# 18_ETH.net
KiCad netlist of a schematic drawn in Altium Designer
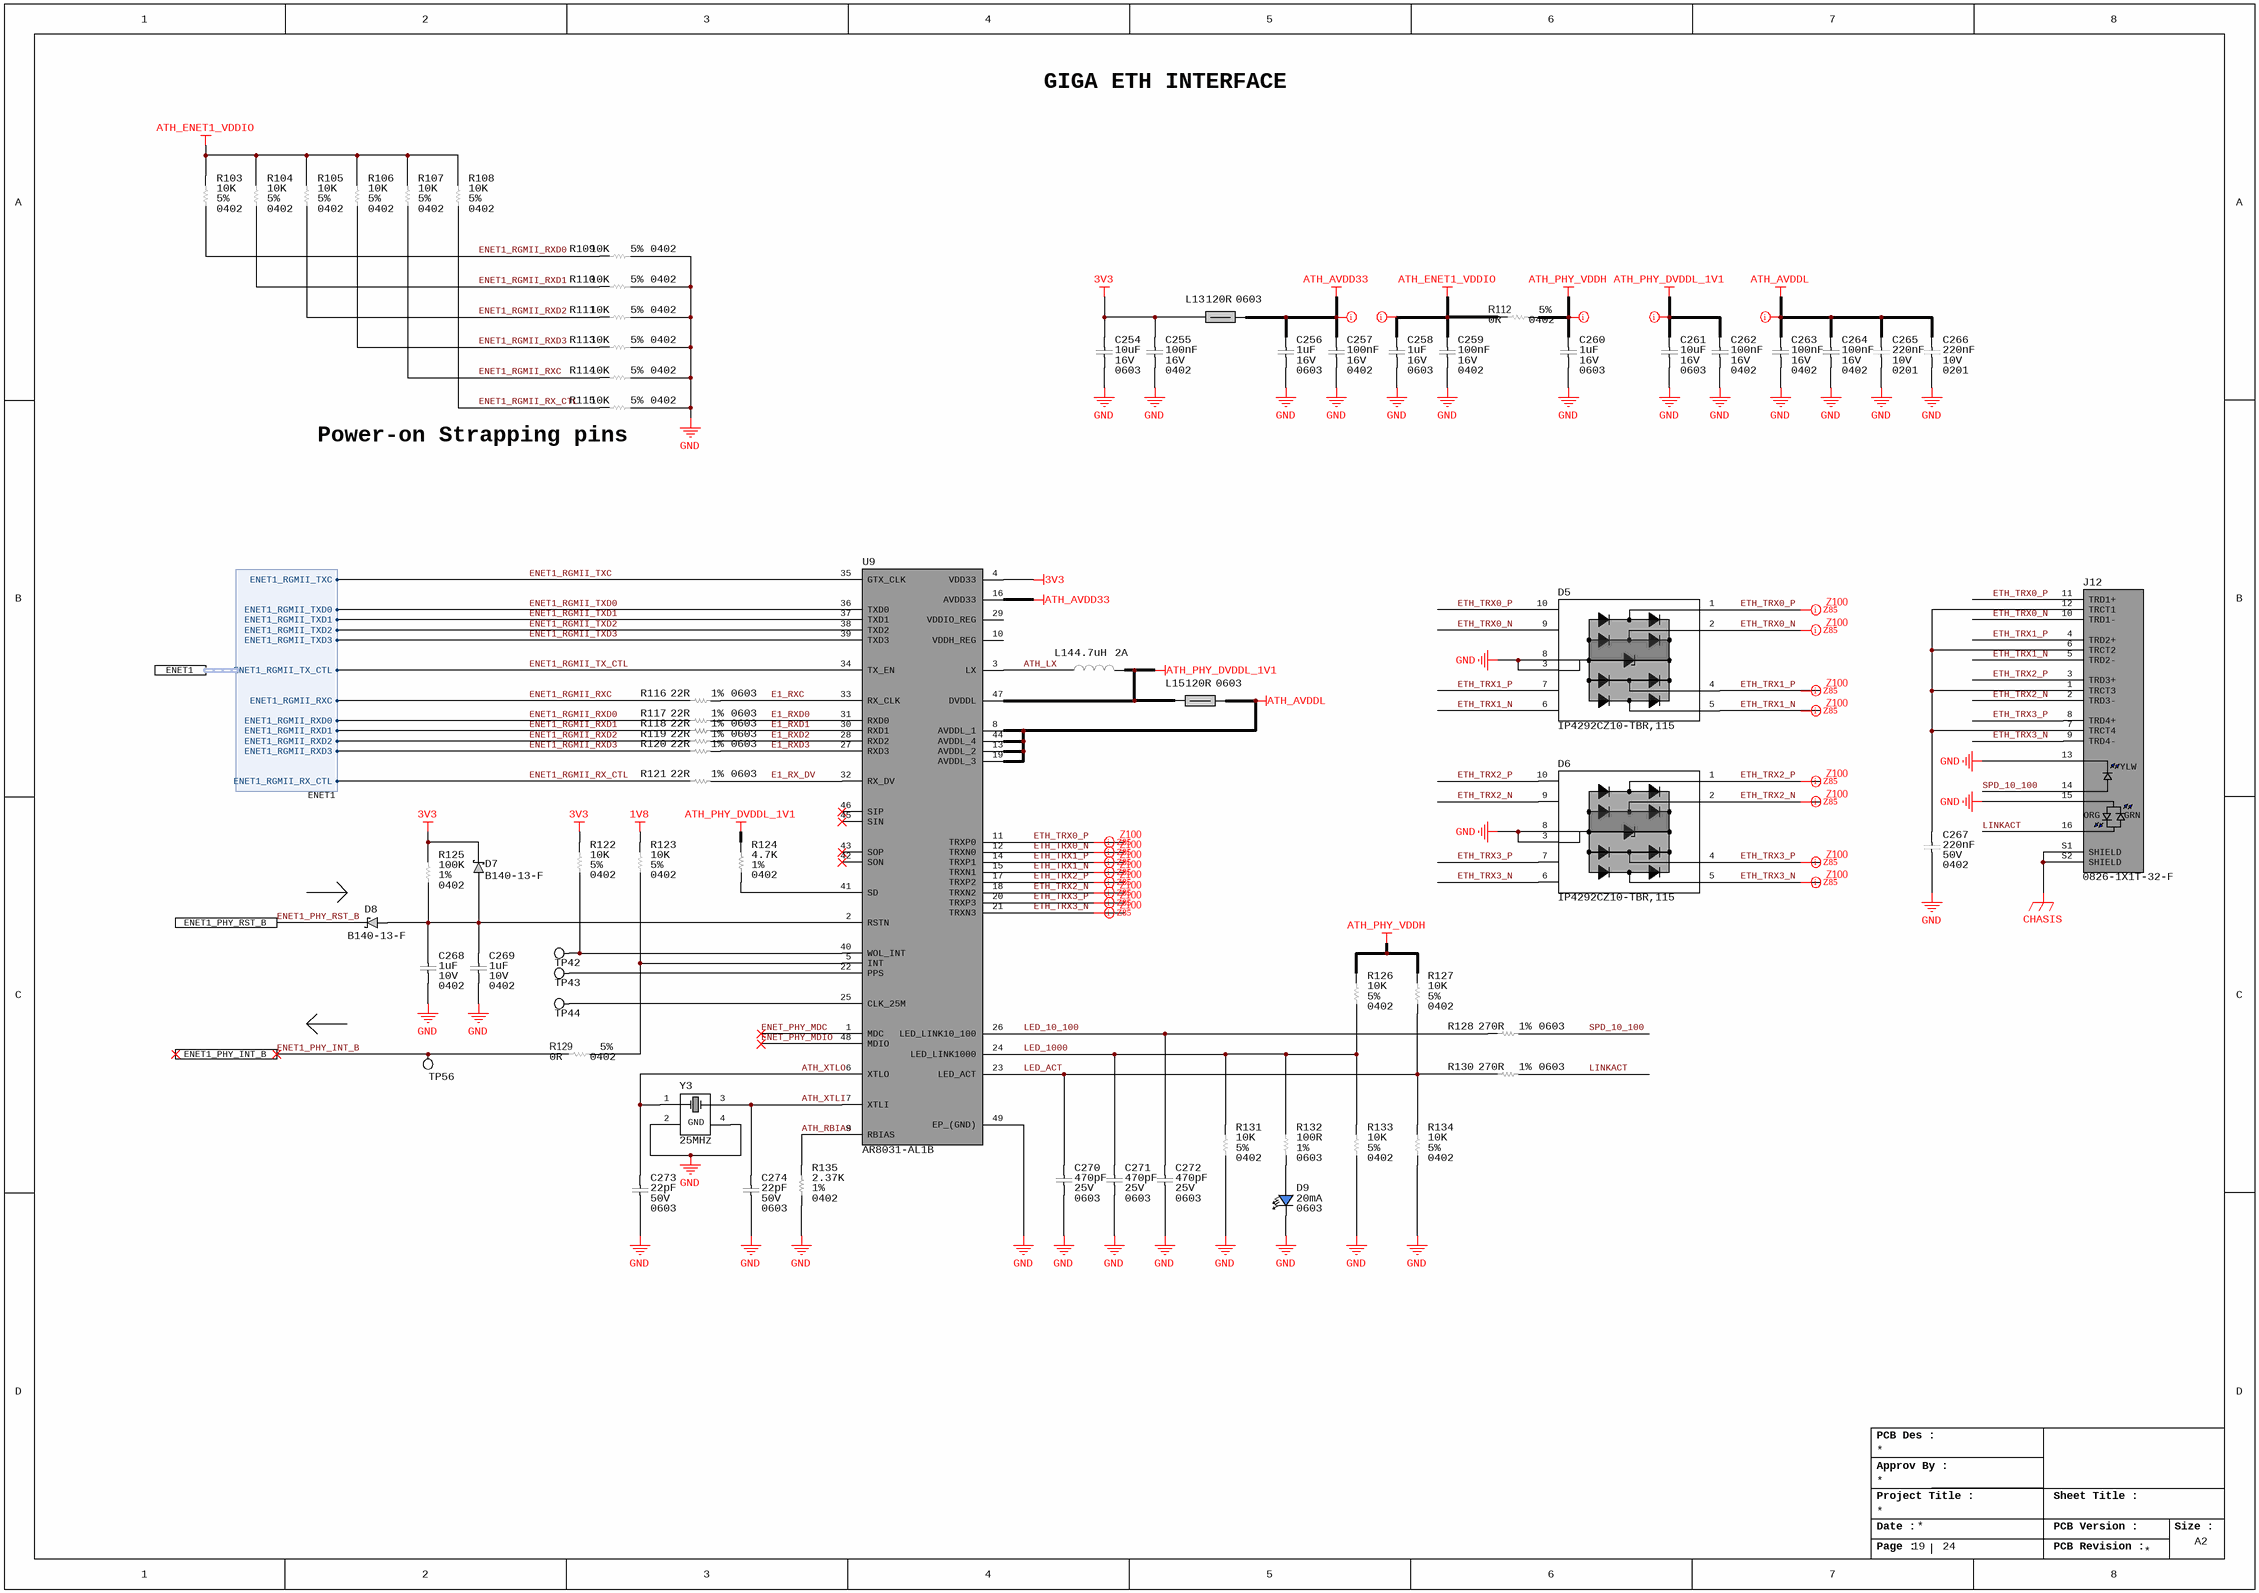
[diagram p0: 18_ETH.SchDoc]

(export (version "E")
  (design (tool "Eeschema 10.0.6"))
  (components
    (comp (ref "C254")
      (value "GRM188R61C106MAALD")
      (footprint "CAP_0603_CAPC1608X08N")
      (description "0603 10 uF 16 V ±20% Tolerance X5R Multilayer Ceramic Chip Capacitor")
      (fields
        (field (name "MANUFACTURER") "Murata")
        (field (name "TOLERANCE") "20%")
        (field (name "VOLTAGE RATING") "16V")
        (field (name "CAPACITANCE") "10uF")
        (field (name "CASE/PACKAGE") "0603")
      )
      (libsource (lib "Electronic Devices_LIB") (part "CAP_10UF_16V_X5R_0603"))
    )
    (comp (ref "C255")
      (value "CL05B104KO5NNNC")
      (footprint "CAP_0402_CAPC1005X05N")
      (description "Multilayer Ceramic Capacitor, 0.1 uF, 16 V, ± 10%, X7R, 0402 [1005 Metric]")
      (fields
        (field (name "MANUFACTURER") "Samsung")
        (field (name "TOLERANCE") "10%")
        (field (name "VOLTAGE RATING") "16V")
        (field (name "CAPACITANCE") "100nF")
        (field (name "CASE/PACKAGE") "0402")
      )
      (libsource (lib "Electronic Devices_LIB") (part "CAP_100NF_16V_X7R_0402"))
    )
    (comp (ref "C256")
      (value "CL10A105KO8NNNC")
      (footprint "CAP_0603_CAPC1608X08N")
      (description "CAP CER 1UF 16V X5R 0603")
      (fields
        (field (name "MANUFACTURER") "Samsung")
        (field (name "TOLERANCE") "10%")
        (field (name "VOLTAGE RATING") "16V")
        (field (name "CAPACITANCE") "1uF")
        (field (name "CASE/PACKAGE") "0603")
      )
      (libsource (lib "Electronic Devices_LIB") (part "CAP_1UF_16V_X5R_0603"))
    )
    (comp (ref "C257")
      (value "CL05B104KO5NNNC")
      (footprint "CAP_0402_CAPC1005X05N")
      (description "Multilayer Ceramic Capacitor, 0.1 uF, 16 V, ± 10%, X7R, 0402 [1005 Metric]")
      (fields
        (field (name "MANUFACTURER") "Samsung")
        (field (name "TOLERANCE") "10%")
        (field (name "VOLTAGE RATING") "16V")
        (field (name "CAPACITANCE") "100nF")
        (field (name "CASE/PACKAGE") "0402")
      )
      (libsource (lib "Electronic Devices_LIB") (part "CAP_100NF_16V_X7R_0402"))
    )
    (comp (ref "C258")
      (value "CL10A105KO8NNNC")
      (footprint "CAP_0603_CAPC1608X08N")
      (description "CAP CER 1UF 16V X5R 0603")
      (fields
        (field (name "MANUFACTURER") "Samsung")
        (field (name "TOLERANCE") "10%")
        (field (name "VOLTAGE RATING") "16V")
        (field (name "CAPACITANCE") "1uF")
        (field (name "CASE/PACKAGE") "0603")
      )
      (libsource (lib "Electronic Devices_LIB") (part "CAP_1UF_16V_X5R_0603"))
    )
    (comp (ref "C259")
      (value "CL05B104KO5NNNC")
      (footprint "CAP_0402_CAPC1005X05N")
      (description "Multilayer Ceramic Capacitor, 0.1 uF, 16 V, ± 10%, X7R, 0402 [1005 Metric]")
      (fields
        (field (name "MANUFACTURER") "Samsung")
        (field (name "TOLERANCE") "10%")
        (field (name "VOLTAGE RATING") "16V")
        (field (name "CAPACITANCE") "100nF")
        (field (name "CASE/PACKAGE") "0402")
      )
      (libsource (lib "Electronic Devices_LIB") (part "CAP_100NF_16V_X7R_0402"))
    )
    (comp (ref "C260")
      (value "CL10A105KO8NNNC")
      (footprint "CAP_0603_CAPC1608X08N")
      (description "CAP CER 1UF 16V X5R 0603")
      (fields
        (field (name "MANUFACTURER") "Samsung")
        (field (name "TOLERANCE") "10%")
        (field (name "VOLTAGE RATING") "16V")
        (field (name "CAPACITANCE") "1uF")
        (field (name "CASE/PACKAGE") "0603")
      )
      (libsource (lib "Electronic Devices_LIB") (part "CAP_1UF_16V_X5R_0603"))
    )
    (comp (ref "C261")
      (value "GRM188R61C106MAALD")
      (footprint "CAP_0603_CAPC1608X08N")
      (description "0603 10 uF 16 V ±20% Tolerance X5R Multilayer Ceramic Chip Capacitor")
      (fields
        (field (name "MANUFACTURER") "Murata")
        (field (name "TOLERANCE") "20%")
        (field (name "VOLTAGE RATING") "16V")
        (field (name "CAPACITANCE") "10uF")
        (field (name "CASE/PACKAGE") "0603")
      )
      (libsource (lib "Electronic Devices_LIB") (part "CAP_10UF_16V_X5R_0603"))
    )
    (comp (ref "C262")
      (value "CL05B104KO5NNNC")
      (footprint "CAP_0402_CAPC1005X05N")
      (description "Multilayer Ceramic Capacitor, 0.1 uF, 16 V, ± 10%, X7R, 0402 [1005 Metric]")
      (fields
        (field (name "MANUFACTURER") "Samsung")
        (field (name "TOLERANCE") "10%")
        (field (name "VOLTAGE RATING") "16V")
        (field (name "CAPACITANCE") "100nF")
        (field (name "CASE/PACKAGE") "0402")
      )
      (libsource (lib "Electronic Devices_LIB") (part "CAP_100NF_16V_X7R_0402"))
    )
    (comp (ref "C263")
      (value "CL05B104KO5NNNC")
      (footprint "CAP_0402_CAPC1005X05N")
      (description "Multilayer Ceramic Capacitor, 0.1 uF, 16 V, ± 10%, X7R, 0402 [1005 Metric]")
      (fields
        (field (name "MANUFACTURER") "Samsung")
        (field (name "TOLERANCE") "10%")
        (field (name "VOLTAGE RATING") "16V")
        (field (name "CAPACITANCE") "100nF")
        (field (name "CASE/PACKAGE") "0402")
      )
      (libsource (lib "Electronic Devices_LIB") (part "CAP_100NF_16V_X7R_0402"))
    )
    (comp (ref "C264")
      (value "CL05B104KO5NNNC")
      (footprint "CAP_0402_CAPC1005X05N")
      (description "Multilayer Ceramic Capacitor, 0.1 uF, 16 V, ± 10%, X7R, 0402 [1005 Metric]")
      (fields
        (field (name "MANUFACTURER") "Samsung")
        (field (name "TOLERANCE") "10%")
        (field (name "VOLTAGE RATING") "16V")
        (field (name "CAPACITANCE") "100nF")
        (field (name "CASE/PACKAGE") "0402")
      )
      (libsource (lib "Electronic Devices_LIB") (part "CAP_100NF_16V_X7R_0402"))
    )
    (comp (ref "C265")
      (value "LMK063BJ224MP-F")
      (footprint "CAP_0201_CAPC0603X03N")
      (description "Multilayer Ceramic Capacitors (High dielectric type), 10V, 0.22 uF, ± 20 %, 0201, X5R, RoHS")
      (fields
        (field (name "MANUFACTURER") "Taiyo Yuden")
        (field (name "TOLERANCE") "20%")
        (field (name "VOLTAGE RATING (DC)") "10V")
        (field (name "CAPACITANCE") "220nF")
        (field (name "CASE/PACKAGE") "0201")
      )
      (libsource (lib "Electronic Devices_LIB") (part "CAP_0.22UF_10V_X5R_0201"))
    )
    (comp (ref "C266")
      (value "LMK063BJ224MP-F")
      (footprint "CAP_0201_CAPC0603X03N")
      (description "Multilayer Ceramic Capacitors (High dielectric type), 10V, 0.22 uF, ± 20 %, 0201, X5R, RoHS")
      (fields
        (field (name "MANUFACTURER") "Taiyo Yuden")
        (field (name "TOLERANCE") "20%")
        (field (name "VOLTAGE RATING (DC)") "10V")
        (field (name "CAPACITANCE") "220nF")
        (field (name "CASE/PACKAGE") "0201")
      )
      (libsource (lib "Electronic Devices_LIB") (part "CAP_0.22UF_10V_X5R_0201"))
    )
    (comp (ref "C267")
      (value "GRM155R61H224KE01W")
      (footprint "CAP_0402_CAPC1005X05N")
      (description "Multilayer Ceramic Capacitor, 0.22 uF, 50 VDC, ± 10%, X5R, 0402 [1005 Metric]")
      (fields
        (field (name "MANUFACTURER") "Murata")
        (field (name "CASE/PACKAGE") "0402")
        (field (name "VOLTAGE RATING (DC)") "50V")
        (field (name "CAPACITANCE") "220nF")
      )
      (libsource (lib "Electronic Devices_LIB") (part "CAP_0.22UF_50V_X5R_0402"))
    )
    (comp (ref "C268")
      (value "GRM155C81A105KA12D")
      (footprint "CAP_0402_CAPC1005X05N")
      (description "0402 10 V 1 uF ±10% Tolerance X6S Multilayer Ceramic Capacitor")
      (fields
        (field (name "MANUFACTURER") "Murata")
        (field (name "TOLERANCE") "10%")
        (field (name "VOLTAGE RATING") "10V")
        (field (name "CAPACITANCE") "1uF")
        (field (name "CASE/PACKAGE") "0402")
      )
      (libsource (lib "Electronic Devices_LIB") (part "CAP_1UF_10V_X6S_0402"))
    )
    (comp (ref "C269")
      (value "GRM155C81A105KA12D")
      (footprint "CAP_0402_CAPC1005X05N")
      (description "0402 10 V 1 uF ±10% Tolerance X6S Multilayer Ceramic Capacitor")
      (fields
        (field (name "MANUFACTURER") "Murata")
        (field (name "TOLERANCE") "10%")
        (field (name "VOLTAGE RATING") "10V")
        (field (name "CAPACITANCE") "1uF")
        (field (name "CASE/PACKAGE") "0402")
      )
      (libsource (lib "Electronic Devices_LIB") (part "CAP_1UF_10V_X6S_0402"))
    )
    (comp (ref "C270")
      (value "C0603C471K3RACTU")
      (footprint "CAP_0603_CAPC1608X08N")
      (fields
        (field (name "MANUFACTURER") "KEMET")
        (field (name "TOLERANCE") "10%")
        (field (name "VOLTAGE RATING") "25V")
        (field (name "CAPACITANCE") "470pF")
        (field (name "CASE CODE (IMPERIAL)") "0603")
      )
      (libsource (lib "Electronic Devices_LIB") (part "CAP_470pF_25V_X7R_0603"))
    )
    (comp (ref "C271")
      (value "C0603C471K3RACTU")
      (footprint "CAP_0603_CAPC1608X08N")
      (fields
        (field (name "MANUFACTURER") "KEMET")
        (field (name "TOLERANCE") "10%")
        (field (name "VOLTAGE RATING") "25V")
        (field (name "CAPACITANCE") "470pF")
        (field (name "CASE CODE (IMPERIAL)") "0603")
      )
      (libsource (lib "Electronic Devices_LIB") (part "CAP_470pF_25V_X7R_0603"))
    )
    (comp (ref "C272")
      (value "C0603C471K3RACTU")
      (footprint "CAP_0603_CAPC1608X08N")
      (fields
        (field (name "MANUFACTURER") "KEMET")
        (field (name "TOLERANCE") "10%")
        (field (name "VOLTAGE RATING") "25V")
        (field (name "CAPACITANCE") "470pF")
        (field (name "CASE CODE (IMPERIAL)") "0603")
      )
      (libsource (lib "Electronic Devices_LIB") (part "CAP_470pF_25V_X7R_0603"))
    )
    (comp (ref "C273")
      (value "C0603C220J5GACTU")
      (footprint "CAP_0603_CAPC1608X08N")
      (description "Multilayer Ceramic Capacitor, 22 pF, 50 V, ï¿½ 5%, C0G (NP0), 0603 [1608 Metric]")
      (fields
        (field (name "MANUFACTURER") "KEMET")
        (field (name "TOLERANCE") "5%")
        (field (name "VOLTAGE RATING (DC)") "50V")
        (field (name "CAPACITANCE") "22pF")
        (field (name "CASE/PACKAGE") "0603")
      )
      (libsource (lib "Electronic Devices_LIB") (part "CAP_22pF_50V_NP0_0603"))
    )
    (comp (ref "C274")
      (value "C0603C220J5GACTU")
      (footprint "CAP_0603_CAPC1608X08N")
      (description "Multilayer Ceramic Capacitor, 22 pF, 50 V, ï¿½ 5%, C0G (NP0), 0603 [1608 Metric]")
      (fields
        (field (name "MANUFACTURER") "KEMET")
        (field (name "TOLERANCE") "5%")
        (field (name "VOLTAGE RATING (DC)") "50V")
        (field (name "CAPACITANCE") "22pF")
        (field (name "CASE/PACKAGE") "0603")
      )
      (libsource (lib "Electronic Devices_LIB") (part "CAP_22pF_50V_NP0_0603"))
    )
    (comp (ref "D5")
      (value "IP4292CZ10-TBR,115")
      (footprint "DIO_TVS_SON50P100X250X50-10N")
      (description "IP4292CZ10 Series 4 Channel 4 V 0.55 pF ESD Protected TVS Diode - DFN2510A-10")
      (fields (field (name "MANUFACTURER") "Nexperia"))
      (libsource (lib "Electronic Devices_LIB") (part "DIO_TVS_4CH_4V_IP4292CZ10-TBR,115"))
    )
    (comp (ref "D6")
      (value "IP4292CZ10-TBR,115")
      (footprint "DIO_TVS_SON50P100X250X50-10N")
      (description "IP4292CZ10 Series 4 Channel 4 V 0.55 pF ESD Protected TVS Diode - DFN2510A-10")
      (fields (field (name "MANUFACTURER") "Nexperia"))
      (libsource (lib "Electronic Devices_LIB") (part "DIO_TVS_4CH_4V_IP4292CZ10-TBR,115"))
    )
    (comp (ref "D7")
      (value "B140-13-F")
      (footprint "DIOM5226X240N")
      (description "Rectifier Diode, Schottky, 1 Phase, 1 Element, 1A, 40V V(RRM), Silicon, DO-214AC")
      (fields (field (name "MANUFACTURER") "Diodes"))
      (libsource (lib "Electronic Devices_LIB") (part "DIO_SCTKY_40V_1A_B140-13-F"))
    )
    (comp (ref "D8")
      (value "B140-13-F")
      (footprint "DIOM5226X240N")
      (description "Rectifier Diode, Schottky, 1 Phase, 1 Element, 1A, 40V V(RRM), Silicon, DO-214AC")
      (fields (field (name "MANUFACTURER") "Diodes"))
      (libsource (lib "Electronic Devices_LIB") (part "DIO_SCTKY_40V_1A_B140-13-F"))
    )
    (comp (ref "D9")
      (value "ASCKCB00-NS3T4010302")
      (footprint "LED_0603-BLUE-0.75mm")
      (description "LED Single Chip Blue 467nm 20mA 2-Pin DFN T/R")
      (fields
        (field (name "MANUFACTURER") "Broadcom")
        (field (name "CASE/PACKCAGE") "0603")
        (field (name "TEST CURRENT") "20mA")
      )
      (libsource (lib "Electronic Devices_LIB") (part "LED_DIO_BLUE_20mA_0603_ASCKCB00-NS3T4010302"))
    )
    (comp (ref "J12")
      (value "0826-1X1T-32-F")
      (footprint "BEL_0826-1X1T-32-F")
      (description "Modular Connectors / Ethernet Connectors RJ45 Connector")
      (fields (field (name "MANUFACTURER") "Bel"))
      (libsource (lib "Electronic Devices_LIB") (part "CONN_RJ45_0826-1X1T-32-F"))
    )
    (comp (ref "L13")
      (value "BLM18PG121SH1D")
      (footprint "IND_0603_INDC1608X08N")
      (description "Ferrite Beads Multi-Layer 120Ohm 25% 100MHz 2A 50mOhm DCR 0603 Automotive Paper T/R")
      (fields
        (field (name "MANUFACTURER") "Murata")
        (field (name "TOLERANCE") "25%")
        (field (name "IMPEDANCE") "120R")
        (field (name "CASE/PACKAGE") "0603")
      )
      (libsource (lib "Electronic Devices_LIB") (part "IND_FERRITE_BEADS_120R_2A_0603_BLM18PG121SH1D"))
    )
    (comp (ref "L14")
      (value "DFE252012P-4R7M=P2")
      (footprint "DFE2HCAH1R0MJ0L")
      (description "Inductor Power Shielded Wirewound 4.7uH 20% 1MHz Metal 1.4A 0.2Ohm DCR 1008 T/R")
      (fields
        (field (name "MANUFACTURER") "Murata")
        (field (name "TOLERANCE") "20%")
        (field (name "CURRENT RATING") "2A")
        (field (name "INDUCTANCE") "4.7uH")
      )
      (libsource (lib "Electronic Devices_LIB") (part "IND_4.7uF_1.4A-DFE252012P-4R7M=P2"))
    )
    (comp (ref "L15")
      (value "BLM18PG121SH1D")
      (footprint "IND_0603_INDC1608X08N")
      (description "Ferrite Beads Multi-Layer 120Ohm 25% 100MHz 2A 50mOhm DCR 0603 Automotive Paper T/R")
      (fields
        (field (name "MANUFACTURER") "Murata")
        (field (name "TOLERANCE") "25%")
        (field (name "IMPEDANCE") "120R")
        (field (name "CASE/PACKAGE") "0603")
      )
      (libsource (lib "Electronic Devices_LIB") (part "IND_FERRITE_BEADS_120R_2A_0603_BLM18PG121SH1D"))
    )
    (comp (ref "R103")
      (value "ERJ-2GEJ103X")
      (footprint "RES_0402_RESC1005X04N")
      (description "Res Thick Film 0402 10K Ohm 5% 1/10W ±200ppm/°C Molded SMD Punched Carrier T/R")
      (fields
        (field (name "MANUFACTURER") "Panasonic")
        (field (name "TOLERANCE") "5%")
        (field (name "RESISTANCE") "10K")
        (field (name "CASE/PACKAGE") "0402")
      )
      (libsource (lib "Electronic Devices_LIB") (part "RES_10K_5%_100mW_0402"))
    )
    (comp (ref "R104")
      (value "ERJ-2GEJ103X")
      (footprint "RES_0402_RESC1005X04N")
      (description "Res Thick Film 0402 10K Ohm 5% 1/10W ±200ppm/°C Molded SMD Punched Carrier T/R")
      (fields
        (field (name "MANUFACTURER") "Panasonic")
        (field (name "TOLERANCE") "5%")
        (field (name "RESISTANCE") "10K")
        (field (name "CASE/PACKAGE") "0402")
      )
      (libsource (lib "Electronic Devices_LIB") (part "RES_10K_5%_100mW_0402"))
    )
    (comp (ref "R105")
      (value "ERJ-2GEJ103X")
      (footprint "RES_0402_RESC1005X04N")
      (description "Res Thick Film 0402 10K Ohm 5% 1/10W ±200ppm/°C Molded SMD Punched Carrier T/R")
      (fields
        (field (name "MANUFACTURER") "Panasonic")
        (field (name "TOLERANCE") "5%")
        (field (name "RESISTANCE") "10K")
        (field (name "CASE/PACKAGE") "0402")
      )
      (libsource (lib "Electronic Devices_LIB") (part "RES_10K_5%_100mW_0402"))
    )
    (comp (ref "R106")
      (value "ERJ-2GEJ103X")
      (footprint "RES_0402_RESC1005X04N")
      (description "Res Thick Film 0402 10K Ohm 5% 1/10W ±200ppm/°C Molded SMD Punched Carrier T/R")
      (fields
        (field (name "MANUFACTURER") "Panasonic")
        (field (name "TOLERANCE") "5%")
        (field (name "RESISTANCE") "10K")
        (field (name "CASE/PACKAGE") "0402")
      )
      (libsource (lib "Electronic Devices_LIB") (part "RES_10K_5%_100mW_0402"))
    )
    (comp (ref "R107")
      (value "ERJ-2GEJ103X")
      (footprint "RES_0402_RESC1005X04N")
      (description "Res Thick Film 0402 10K Ohm 5% 1/10W ±200ppm/°C Molded SMD Punched Carrier T/R")
      (fields
        (field (name "MANUFACTURER") "Panasonic")
        (field (name "TOLERANCE") "5%")
        (field (name "RESISTANCE") "10K")
        (field (name "CASE/PACKAGE") "0402")
      )
      (libsource (lib "Electronic Devices_LIB") (part "RES_10K_5%_100mW_0402"))
    )
    (comp (ref "R108")
      (value "ERJ-2GEJ103X")
      (footprint "RES_0402_RESC1005X04N")
      (description "Res Thick Film 0402 10K Ohm 5% 1/10W ±200ppm/°C Molded SMD Punched Carrier T/R")
      (fields
        (field (name "MANUFACTURER") "Panasonic")
        (field (name "TOLERANCE") "5%")
        (field (name "RESISTANCE") "10K")
        (field (name "CASE/PACKAGE") "0402")
      )
      (libsource (lib "Electronic Devices_LIB") (part "RES_10K_5%_100mW_0402"))
    )
    (comp (ref "R109")
      (value "ERJ-2GEJ103X")
      (footprint "RES_0402_RESC1005X04N")
      (description "Res Thick Film 0402 10K Ohm 5% 1/10W ±200ppm/°C Molded SMD Punched Carrier T/R")
      (fields
        (field (name "MANUFACTURER") "Panasonic")
        (field (name "TOLERANCE") "5%")
        (field (name "RESISTANCE") "10K")
        (field (name "CASE/PACKAGE") "0402")
      )
      (libsource (lib "Electronic Devices_LIB") (part "RES_10K_5%_100mW_0402"))
    )
    (comp (ref "R110")
      (value "ERJ-2GEJ103X")
      (footprint "RES_0402_RESC1005X04N")
      (description "Res Thick Film 0402 10K Ohm 5% 1/10W ±200ppm/°C Molded SMD Punched Carrier T/R")
      (fields
        (field (name "MANUFACTURER") "Panasonic")
        (field (name "TOLERANCE") "5%")
        (field (name "RESISTANCE") "10K")
        (field (name "CASE/PACKAGE") "0402")
      )
      (libsource (lib "Electronic Devices_LIB") (part "RES_10K_5%_100mW_0402"))
    )
    (comp (ref "R111")
      (value "ERJ-2GEJ103X")
      (footprint "RES_0402_RESC1005X04N")
      (description "Res Thick Film 0402 10K Ohm 5% 1/10W ±200ppm/°C Molded SMD Punched Carrier T/R")
      (fields
        (field (name "MANUFACTURER") "Panasonic")
        (field (name "TOLERANCE") "5%")
        (field (name "RESISTANCE") "10K")
        (field (name "CASE/PACKAGE") "0402")
      )
      (libsource (lib "Electronic Devices_LIB") (part "RES_10K_5%_100mW_0402"))
    )
    (comp (ref "R112")
      (value "ERJ-2GE0R00X")
      (footprint "RES_0402_RESC1005X04N")
      (description "SMD Chip Resistor, Jumper, 0 ohm, 100 mW, 0402 [1005 Metric], Thick Film, General Purpose")
      (fields
        (field (name "MANUFACTURER") "Panasonic")
        (field (name "CASE CODE (IMPERIAL)") "0402")
        (field (name "TOLERANCE") "5%")
        (field (name "RESISTANCE") "0R")
      )
      (libsource (lib "Electronic Devices_LIB") (part "RES_0R_5%_100mW_0402"))
    )
    (comp (ref "R113")
      (value "ERJ-2GEJ103X")
      (footprint "RES_0402_RESC1005X04N")
      (description "Res Thick Film 0402 10K Ohm 5% 1/10W ±200ppm/°C Molded SMD Punched Carrier T/R")
      (fields
        (field (name "MANUFACTURER") "Panasonic")
        (field (name "TOLERANCE") "5%")
        (field (name "RESISTANCE") "10K")
        (field (name "CASE/PACKAGE") "0402")
      )
      (libsource (lib "Electronic Devices_LIB") (part "RES_10K_5%_100mW_0402"))
    )
    (comp (ref "R114")
      (value "ERJ-2GEJ103X")
      (footprint "RES_0402_RESC1005X04N")
      (description "Res Thick Film 0402 10K Ohm 5% 1/10W ±200ppm/°C Molded SMD Punched Carrier T/R")
      (fields
        (field (name "MANUFACTURER") "Panasonic")
        (field (name "TOLERANCE") "5%")
        (field (name "RESISTANCE") "10K")
        (field (name "CASE/PACKAGE") "0402")
      )
      (libsource (lib "Electronic Devices_LIB") (part "RES_10K_5%_100mW_0402"))
    )
    (comp (ref "R115")
      (value "ERJ-2GEJ103X")
      (footprint "RES_0402_RESC1005X04N")
      (description "Res Thick Film 0402 10K Ohm 5% 1/10W ±200ppm/°C Molded SMD Punched Carrier T/R")
      (fields
        (field (name "MANUFACTURER") "Panasonic")
        (field (name "TOLERANCE") "5%")
        (field (name "RESISTANCE") "10K")
        (field (name "CASE/PACKAGE") "0402")
      )
      (libsource (lib "Electronic Devices_LIB") (part "RES_10K_5%_100mW_0402"))
    )
    (comp (ref "R116")
      (value "RC0603FR-0722RL")
      (footprint "RES_0603_RESC1608X04N")
      (description "Res Thick Film 0603 22 Ohm 1% 0.1W(1/10W) ±100ppm/C Pad SMD T/R")
      (fields
        (field (name "MANUFACTURER") "Yageo")
        (field (name "TOLERANCE") "1%")
        (field (name "RESISTANCE") "22R")
        (field (name "CASE/PACKAGE") "0603")
      )
      (libsource (lib "Electronic Devices_LIB") (part "RES_22R_1%_100mW_0603"))
    )
    (comp (ref "R117")
      (value "RC0603FR-0722RL")
      (footprint "RES_0603_RESC1608X04N")
      (description "Res Thick Film 0603 22 Ohm 1% 0.1W(1/10W) ±100ppm/C Pad SMD T/R")
      (fields
        (field (name "MANUFACTURER") "Yageo")
        (field (name "TOLERANCE") "1%")
        (field (name "RESISTANCE") "22R")
        (field (name "CASE/PACKAGE") "0603")
      )
      (libsource (lib "Electronic Devices_LIB") (part "RES_22R_1%_100mW_0603"))
    )
    (comp (ref "R118")
      (value "RC0603FR-0722RL")
      (footprint "RES_0603_RESC1608X04N")
      (description "Res Thick Film 0603 22 Ohm 1% 0.1W(1/10W) ±100ppm/C Pad SMD T/R")
      (fields
        (field (name "MANUFACTURER") "Yageo")
        (field (name "TOLERANCE") "1%")
        (field (name "RESISTANCE") "22R")
        (field (name "CASE/PACKAGE") "0603")
      )
      (libsource (lib "Electronic Devices_LIB") (part "RES_22R_1%_100mW_0603"))
    )
    (comp (ref "R119")
      (value "RC0603FR-0722RL")
      (footprint "RES_0603_RESC1608X04N")
      (description "Res Thick Film 0603 22 Ohm 1% 0.1W(1/10W) ±100ppm/C Pad SMD T/R")
      (fields
        (field (name "MANUFACTURER") "Yageo")
        (field (name "TOLERANCE") "1%")
        (field (name "RESISTANCE") "22R")
        (field (name "CASE/PACKAGE") "0603")
      )
      (libsource (lib "Electronic Devices_LIB") (part "RES_22R_1%_100mW_0603"))
    )
    (comp (ref "R120")
      (value "RC0603FR-0722RL")
      (footprint "RES_0603_RESC1608X04N")
      (description "Res Thick Film 0603 22 Ohm 1% 0.1W(1/10W) ±100ppm/C Pad SMD T/R")
      (fields
        (field (name "MANUFACTURER") "Yageo")
        (field (name "TOLERANCE") "1%")
        (field (name "RESISTANCE") "22R")
        (field (name "CASE/PACKAGE") "0603")
      )
      (libsource (lib "Electronic Devices_LIB") (part "RES_22R_1%_100mW_0603"))
    )
    (comp (ref "R121")
      (value "RC0603FR-0722RL")
      (footprint "RES_0603_RESC1608X04N")
      (description "Res Thick Film 0603 22 Ohm 1% 0.1W(1/10W) ±100ppm/C Pad SMD T/R")
      (fields
        (field (name "MANUFACTURER") "Yageo")
        (field (name "TOLERANCE") "1%")
        (field (name "RESISTANCE") "22R")
        (field (name "CASE/PACKAGE") "0603")
      )
      (libsource (lib "Electronic Devices_LIB") (part "RES_22R_1%_100mW_0603"))
    )
    (comp (ref "R122")
      (value "ERJ-2GEJ103X")
      (footprint "RES_0402_RESC1005X04N")
      (description "Res Thick Film 0402 10K Ohm 5% 1/10W ±200ppm/°C Molded SMD Punched Carrier T/R")
      (fields
        (field (name "MANUFACTURER") "Panasonic")
        (field (name "TOLERANCE") "5%")
        (field (name "RESISTANCE") "10K")
        (field (name "CASE/PACKAGE") "0402")
      )
      (libsource (lib "Electronic Devices_LIB") (part "RES_10K_5%_100mW_0402"))
    )
    (comp (ref "R123")
      (value "ERJ-2GEJ103X")
      (footprint "RES_0402_RESC1005X04N")
      (description "Res Thick Film 0402 10K Ohm 5% 1/10W ±200ppm/°C Molded SMD Punched Carrier T/R")
      (fields
        (field (name "MANUFACTURER") "Panasonic")
        (field (name "TOLERANCE") "5%")
        (field (name "RESISTANCE") "10K")
        (field (name "CASE/PACKAGE") "0402")
      )
      (libsource (lib "Electronic Devices_LIB") (part "RES_10K_5%_100mW_0402"))
    )
    (comp (ref "R124")
      (value "ERJ-2RKF4701X")
      (footprint "RES_0402_RESC1005X04N")
      (description "Res Thick Film 0402 4.7K Ohm 1% 0.1W ±100ppm/°C Molded SMD Punched Carrier T/R")
      (fields
        (field (name "MANUFACTURER") "Panasonic")
        (field (name "TOLERANCE") "1%")
        (field (name "CASE CODE (IMPERIAL)") "0402")
        (field (name "RESISTANCE") "4.7K")
      )
      (libsource (lib "Electronic Devices_LIB") (part "RES_4.7K_1%_100mW_0402"))
    )
    (comp (ref "R125")
      (value "RC0402FR-07100KL")
      (footprint "RES_0402_RESC1005X04N")
      (description "SMD Chip Resistor, 100 kOhm, ± 1%, 63 mW, 0402 [1005 Metric], Thick Film, General Purpose")
      (fields
        (field (name "MANUFACTURER") "Yageo")
        (field (name "RESISTANCE") "100K")
        (field (name "TOLERANCE") "1%")
        (field (name "CASE/PACKAGE") "0402")
      )
      (libsource (lib "Electronic Devices_LIB") (part "RES_100K_1%_100mW_0402"))
    )
    (comp (ref "R126")
      (value "ERJ-2GEJ103X")
      (footprint "RES_0402_RESC1005X04N")
      (description "Res Thick Film 0402 10K Ohm 5% 1/10W ±200ppm/°C Molded SMD Punched Carrier T/R")
      (fields
        (field (name "MANUFACTURER") "Panasonic")
        (field (name "TOLERANCE") "5%")
        (field (name "RESISTANCE") "10K")
        (field (name "CASE/PACKAGE") "0402")
      )
      (libsource (lib "Electronic Devices_LIB") (part "RES_10K_5%_100mW_0402"))
    )
    (comp (ref "R127")
      (value "ERJ-2GEJ103X")
      (footprint "RES_0402_RESC1005X04N")
      (description "Res Thick Film 0402 10K Ohm 5% 1/10W ±200ppm/°C Molded SMD Punched Carrier T/R")
      (fields
        (field (name "MANUFACTURER") "Panasonic")
        (field (name "TOLERANCE") "5%")
        (field (name "RESISTANCE") "10K")
        (field (name "CASE/PACKAGE") "0402")
      )
      (libsource (lib "Electronic Devices_LIB") (part "RES_10K_5%_100mW_0402"))
    )
    (comp (ref "R128")
      (value "RC0603FR-07270RL")
      (footprint "RES_0603_RESC1608X04N")
      (description "SMD Chip Resistor, 270 Ohm, ï¿½ 1%, 100 mW, 0603 [1608 Metric], Thick Film, General Purpose")
      (fields
        (field (name "MANUFACTURER") "Yageo")
        (field (name "TOLERANCE") "1%")
        (field (name "RESISTANCE") "270R")
        (field (name "CASE/PACKAGE") "0603")
      )
      (libsource (lib "Electronic Devices_LIB") (part "RES_270R_1%_100mW_0603"))
    )
    (comp (ref "R129")
      (value "ERJ-2GE0R00X")
      (footprint "RES_0402_RESC1005X04N")
      (description "SMD Chip Resistor, Jumper, 0 ohm, 100 mW, 0402 [1005 Metric], Thick Film, General Purpose")
      (fields
        (field (name "MANUFACTURER") "Panasonic")
        (field (name "CASE CODE (IMPERIAL)") "0402")
        (field (name "TOLERANCE") "5%")
        (field (name "RESISTANCE") "0R")
      )
      (libsource (lib "Electronic Devices_LIB") (part "RES_0R_5%_100mW_0402"))
    )
    (comp (ref "R130")
      (value "RC0603FR-07270RL")
      (footprint "RES_0603_RESC1608X04N")
      (description "SMD Chip Resistor, 270 Ohm, ï¿½ 1%, 100 mW, 0603 [1608 Metric], Thick Film, General Purpose")
      (fields
        (field (name "MANUFACTURER") "Yageo")
        (field (name "TOLERANCE") "1%")
        (field (name "RESISTANCE") "270R")
        (field (name "CASE/PACKAGE") "0603")
      )
      (libsource (lib "Electronic Devices_LIB") (part "RES_270R_1%_100mW_0603"))
    )
    (comp (ref "R131")
      (value "ERJ-2GEJ103X")
      (footprint "RES_0402_RESC1005X04N")
      (description "Res Thick Film 0402 10K Ohm 5% 1/10W ±200ppm/°C Molded SMD Punched Carrier T/R")
      (fields
        (field (name "MANUFACTURER") "Panasonic")
        (field (name "TOLERANCE") "5%")
        (field (name "RESISTANCE") "10K")
        (field (name "CASE/PACKAGE") "0402")
      )
      (libsource (lib "Electronic Devices_LIB") (part "RES_10K_5%_100mW_0402"))
    )
    (comp (ref "R132")
      (value "ERJ3EKF1000V")
      (footprint "CAP_0603_CAPC1608X08N")
      (description "Res Thick Film 0603 100 Ohm 1% 1/10W ±100ppm/°C Molded SMD Punched Carrier T/R")
      (fields
        (field (name "MANUFACTURER") "Panasonic")
        (field (name "CASE CODE (IMPERIAL)") "0603")
        (field (name "TOLERANCE") "1%")
        (field (name "RESISTANCE") "100R")
      )
      (libsource (lib "Electronic Devices_LIB") (part "RES_100R_1%_100MW_0603"))
    )
    (comp (ref "R133")
      (value "ERJ-2GEJ103X")
      (footprint "RES_0402_RESC1005X04N")
      (description "Res Thick Film 0402 10K Ohm 5% 1/10W ±200ppm/°C Molded SMD Punched Carrier T/R")
      (fields
        (field (name "MANUFACTURER") "Panasonic")
        (field (name "TOLERANCE") "5%")
        (field (name "RESISTANCE") "10K")
        (field (name "CASE/PACKAGE") "0402")
      )
      (libsource (lib "Electronic Devices_LIB") (part "RES_10K_5%_100mW_0402"))
    )
    (comp (ref "R134")
      (value "ERJ-2GEJ103X")
      (footprint "RES_0402_RESC1005X04N")
      (description "Res Thick Film 0402 10K Ohm 5% 1/10W ±200ppm/°C Molded SMD Punched Carrier T/R")
      (fields
        (field (name "MANUFACTURER") "Panasonic")
        (field (name "TOLERANCE") "5%")
        (field (name "RESISTANCE") "10K")
        (field (name "CASE/PACKAGE") "0402")
      )
      (libsource (lib "Electronic Devices_LIB") (part "RES_10K_5%_100mW_0402"))
    )
    (comp (ref "R135")
      (value "ERJ-2RKF2371X")
      (footprint "RES_0402_RESC1005X04N")
      (description "Res Thick Film 0402 2.37K Ohm 1% 1/10W ±100ppm/°C Molded SMD Punched Carrier T/R")
      (fields
        (field (name "MANUFACTURER") "Panasonic")
        (field (name "TOLERANCE") "1%")
        (field (name "RESISTANCE") "2.37K")
        (field (name "CASE/PACKAGE") "0402")
      )
      (libsource (lib "Electronic Devices_LIB") (part "RES_2.37K_1%_100mW_0402"))
    )
    (comp (ref "TP42")
      (value "NO COMPONENT")
      (footprint "TP_PAD_0.5MM_SMD_ROUND")
      (description "Test Point, SMD pad, round, 1.5mm, 1.6mm, 3mm diameter")
      (libsource (lib "Electronic Devices_LIB") (part "TP_PAD_SMD_SMALL"))
    )
    (comp (ref "TP43")
      (value "NO COMPONENT")
      (footprint "TP_PAD_0.5MM_SMD_ROUND")
      (description "Test Point, SMD pad, round, 1.5mm, 1.6mm, 3mm diameter")
      (libsource (lib "Electronic Devices_LIB") (part "TP_PAD_SMD_SMALL"))
    )
    (comp (ref "TP44")
      (value "NO COMPONENT")
      (footprint "TP_PAD_0.5MM_SMD_ROUND")
      (description "Test Point, SMD pad, round, 1.5mm, 1.6mm, 3mm diameter")
      (libsource (lib "Electronic Devices_LIB") (part "TP_PAD_SMD_SMALL"))
    )
    (comp (ref "TP56")
      (value "NO COMPONENT")
      (footprint "TP_PAD_0.5MM_SMD_ROUND")
      (description "Test Point, SMD pad, round, 1.5mm, 1.6mm, 3mm diameter")
      (libsource (lib "Electronic Devices_LIB") (part "TP_PAD_SMD_SMALL"))
    )
    (comp (ref "U9")
      (value "AR8031-AL1B")
      (footprint "QFN40P600X600X80-49N")
      (description "IC TRANSCEIVER ETHERNET 48-QFN / PHY 10Mbps/100Mbps/1Gbps 3.3V 48-Pin QFN EP Tray")
      (fields (field (name "MANUFACTURER") "Qualcomm"))
      (libsource (lib "Electronic Devices_LIB") (part "IC_TRANSCEIVER_ETH_AR8031-AL1B"))
    )
    (comp (ref "Y3")
      (value "405C35B25M00000")
      (footprint "405C35B25M00000")
      (description "405 Series 25 MHz ±30 ppm 13 pF -20 to +70 °C Surface Mount Quartz Crystal")
      (fields
        (field (name "MANUFACTURER") "CTS")
        (field (name "FREQUENCY") "25MHz")
        (field (name "TOLERANCE") "30ppm")
      )
      (libsource (lib "Electronic Devices_LIB") (part "CRYSTAL_25MHZ_13PF_405C35B25M00000"))
    )
  )
  (nets
    (net (code "2") (name "/ATH_LX") (class "Default")
      (node (ref "L14") (pin "1") (pinfunction "1_1") (pintype "passive"))
      (node (ref "U9") (pin "3") (pinfunction "LX_3") (pintype "passive"))
    )
    (net (code "3") (name "/ATH_RBIAS") (class "Default")
      (node (ref "R135") (pin "2") (pinfunction "2_2") (pintype "passive"))
      (node (ref "U9") (pin "9") (pinfunction "RBIAS_9") (pintype "passive"))
    )
    (net (code "4") (name "/ATH_XTLI") (class "Default")
      (node (ref "C274") (pin "2") (pinfunction "2_2") (pintype "passive"))
      (node (ref "U9") (pin "7") (pinfunction "XTLI_7") (pintype "passive"))
      (node (ref "Y3") (pin "3") (pinfunction "XTAL_2_3") (pintype "passive"))
    )
    (net (code "5") (name "/ATH_XTLO") (class "Default")
      (node (ref "C273") (pin "2") (pinfunction "2_2") (pintype "passive"))
      (node (ref "U9") (pin "6") (pinfunction "XTLO_6") (pintype "passive"))
      (node (ref "Y3") (pin "1") (pinfunction "XTAL_1_1") (pintype "passive"))
    )
    (net (code "6") (name "/E1_RXC") (class "Default")
      (node (ref "R116") (pin "2") (pinfunction "2_2") (pintype "passive"))
      (node (ref "U9") (pin "33") (pinfunction "RX_CLK_33") (pintype "passive"))
    )
    (net (code "7") (name "/E1_RXD0") (class "Default")
      (node (ref "R117") (pin "2") (pinfunction "2_2") (pintype "passive"))
      (node (ref "U9") (pin "31") (pinfunction "RXD0_31") (pintype "passive"))
    )
    (net (code "8") (name "/E1_RXD1") (class "Default")
      (node (ref "R118") (pin "2") (pinfunction "2_2") (pintype "passive"))
      (node (ref "U9") (pin "30") (pinfunction "RXD1_30") (pintype "passive"))
    )
    (net (code "9") (name "/E1_RXD2") (class "Default")
      (node (ref "R119") (pin "2") (pinfunction "2_2") (pintype "passive"))
      (node (ref "U9") (pin "28") (pinfunction "RXD2_28") (pintype "passive"))
    )
    (net (code "10") (name "/E1_RXD3") (class "Default")
      (node (ref "R120") (pin "2") (pinfunction "2_2") (pintype "passive"))
      (node (ref "U9") (pin "27") (pinfunction "RXD3_27") (pintype "passive"))
    )
    (net (code "11") (name "/E1_RX_DV") (class "Default")
      (node (ref "R121") (pin "2") (pinfunction "2_2") (pintype "passive"))
      (node (ref "U9") (pin "32") (pinfunction "RX_DV_32") (pintype "passive"))
    )
    (net (code "12") (name "/ENET1_PHY_INT_B") (class "Default")
      (node (ref "R129") (pin "1") (pinfunction "1_1") (pintype "passive"))
      (node (ref "TP56") (pin "1") (pinfunction "1_1") (pintype "passive"))
    )
    (net (code "13") (name "/ENET1_PHY_RST_B") (class "Default")
      (node (ref "D8") (pin "1") (pinfunction "K_1") (pintype "passive"))
    )
    (net (code "14") (name "/ENET1_RGMII_RXC") (class "Default")
      (node (ref "R107") (pin "1") (pinfunction "1_1") (pintype "passive"))
      (node (ref "R114") (pin "2") (pinfunction "2_2") (pintype "passive"))
      (node (ref "R116") (pin "1") (pinfunction "1_1") (pintype "passive"))
    )
    (net (code "15") (name "/ENET1_RGMII_RXD0") (class "Default")
      (node (ref "R103") (pin "1") (pinfunction "1_1") (pintype "passive"))
      (node (ref "R109") (pin "2") (pinfunction "2_2") (pintype "passive"))
      (node (ref "R117") (pin "1") (pinfunction "1_1") (pintype "passive"))
    )
    (net (code "16") (name "/ENET1_RGMII_RXD1") (class "Default")
      (node (ref "R104") (pin "1") (pinfunction "1_1") (pintype "passive"))
      (node (ref "R110") (pin "2") (pinfunction "2_2") (pintype "passive"))
      (node (ref "R118") (pin "1") (pinfunction "1_1") (pintype "passive"))
    )
    (net (code "17") (name "/ENET1_RGMII_RXD2") (class "Default")
      (node (ref "R105") (pin "1") (pinfunction "1_1") (pintype "passive"))
      (node (ref "R111") (pin "2") (pinfunction "2_2") (pintype "passive"))
      (node (ref "R119") (pin "1") (pinfunction "1_1") (pintype "passive"))
    )
    (net (code "18") (name "/ENET1_RGMII_RXD3") (class "Default")
      (node (ref "R106") (pin "1") (pinfunction "1_1") (pintype "passive"))
      (node (ref "R113") (pin "2") (pinfunction "2_2") (pintype "passive"))
      (node (ref "R120") (pin "1") (pinfunction "1_1") (pintype "passive"))
    )
    (net (code "19") (name "/ENET1_RGMII_RX_CTL") (class "Default")
      (node (ref "R108") (pin "1") (pinfunction "1_1") (pintype "passive"))
      (node (ref "R115") (pin "2") (pinfunction "2_2") (pintype "passive"))
      (node (ref "R121") (pin "1") (pinfunction "1_1") (pintype "passive"))
    )
    (net (code "20") (name "/ENET1_RGMII_TXC") (class "Default")
      (node (ref "U9") (pin "35") (pinfunction "GTX_CLK_35") (pintype "passive"))
    )
    (net (code "21") (name "/ENET1_RGMII_TXD0") (class "Default")
      (node (ref "U9") (pin "36") (pinfunction "TXD0_36") (pintype "passive"))
    )
    (net (code "22") (name "/ENET1_RGMII_TXD1") (class "Default")
      (node (ref "U9") (pin "37") (pinfunction "TXD1_37") (pintype "passive"))
    )
    (net (code "23") (name "/ENET1_RGMII_TXD2") (class "Default")
      (node (ref "U9") (pin "38") (pinfunction "TXD2_38") (pintype "passive"))
    )
    (net (code "24") (name "/ENET1_RGMII_TXD3") (class "Default")
      (node (ref "U9") (pin "39") (pinfunction "TXD3_39") (pintype "passive"))
    )
    (net (code "25") (name "/ENET1_RGMII_TX_CTL") (class "Default")
      (node (ref "U9") (pin "34") (pinfunction "TX_EN_34") (pintype "passive"))
    )
    (net (code "26") (name "/ENET_PHY_MDC") (class "Default")
      (node (ref "U9") (pin "1") (pinfunction "MDC_1") (pintype "passive+no_connect"))
    )
    (net (code "27") (name "/ENET_PHY_MDIO") (class "Default")
      (node (ref "U9") (pin "48") (pinfunction "MDIO_48") (pintype "passive+no_connect"))
    )
    (net (code "28") (name "/ETH_TRX0_N") (class "Default")
      (node (ref "D5") (pin "2") (pinfunction "CH2_2") (pintype "passive"))
      (node (ref "D5") (pin "9") (pinfunction "NC3_9") (pintype "passive"))
      (node (ref "J12") (pin "10") (pinfunction "TRD1-_10") (pintype "passive"))
      (node (ref "U9") (pin "12") (pinfunction "TRXN0_12") (pintype "passive"))
    )
    (net (code "29") (name "/ETH_TRX0_P") (class "Default")
      (node (ref "D5") (pin "1") (pinfunction "CH1_1") (pintype "passive"))
      (node (ref "D5") (pin "10") (pinfunction "NC4_10") (pintype "passive"))
      (node (ref "J12") (pin "11") (pinfunction "TRD1+_11") (pintype "passive"))
      (node (ref "U9") (pin "11") (pinfunction "TRXP0_11") (pintype "passive"))
    )
    (net (code "30") (name "/ETH_TRX1_N") (class "Default")
      (node (ref "D5") (pin "5") (pinfunction "CH4_5") (pintype "passive"))
      (node (ref "D5") (pin "6") (pinfunction "NC1_6") (pintype "passive"))
      (node (ref "J12") (pin "5") (pinfunction "TRD2-_5") (pintype "passive"))
      (node (ref "U9") (pin "15") (pinfunction "TRXN1_15") (pintype "passive"))
    )
    (net (code "31") (name "/ETH_TRX1_P") (class "Default")
      (node (ref "D5") (pin "4") (pinfunction "CH3_4") (pintype "passive"))
      (node (ref "D5") (pin "7") (pinfunction "NC2_7") (pintype "passive"))
      (node (ref "J12") (pin "4") (pinfunction "TRD2+_4") (pintype "passive"))
      (node (ref "U9") (pin "14") (pinfunction "TRXP1_14") (pintype "passive"))
    )
    (net (code "32") (name "/ETH_TRX2_N") (class "Default")
      (node (ref "D6") (pin "2") (pinfunction "CH2_2") (pintype "passive"))
      (node (ref "D6") (pin "9") (pinfunction "NC3_9") (pintype "passive"))
      (node (ref "J12") (pin "2") (pinfunction "TRD3-_2") (pintype "passive"))
      (node (ref "U9") (pin "18") (pinfunction "TRXN2_18") (pintype "passive"))
    )
    (net (code "33") (name "/ETH_TRX2_P") (class "Default")
      (node (ref "D6") (pin "1") (pinfunction "CH1_1") (pintype "passive"))
      (node (ref "D6") (pin "10") (pinfunction "NC4_10") (pintype "passive"))
      (node (ref "J12") (pin "3") (pinfunction "TRD3+_3") (pintype "passive"))
      (node (ref "U9") (pin "17") (pinfunction "TRXP2_17") (pintype "passive"))
    )
    (net (code "34") (name "/ETH_TRX3_N") (class "Default")
      (node (ref "D6") (pin "5") (pinfunction "CH4_5") (pintype "passive"))
      (node (ref "D6") (pin "6") (pinfunction "NC1_6") (pintype "passive"))
      (node (ref "J12") (pin "9") (pinfunction "TRD4-_9") (pintype "passive"))
      (node (ref "U9") (pin "21") (pinfunction "TRXN3_21") (pintype "passive"))
    )
    (net (code "35") (name "/ETH_TRX3_P") (class "Default")
      (node (ref "D6") (pin "4") (pinfunction "CH3_4") (pintype "passive"))
      (node (ref "D6") (pin "7") (pinfunction "NC2_7") (pintype "passive"))
      (node (ref "J12") (pin "8") (pinfunction "TRD4+_8") (pintype "passive"))
      (node (ref "U9") (pin "20") (pinfunction "TRXP3_20") (pintype "passive"))
    )
    (net (code "36") (name "/LED_10_100") (class "Default")
      (node (ref "C272") (pin "2") (pinfunction "2_2") (pintype "passive"))
      (node (ref "R128") (pin "1") (pinfunction "1_1") (pintype "passive"))
      (node (ref "U9") (pin "26") (pinfunction "LED_LINK10_100_26") (pintype "passive"))
    )
    (net (code "37") (name "/LED_1000") (class "Default")
      (node (ref "C271") (pin "2") (pinfunction "2_2") (pintype "passive"))
      (node (ref "R126") (pin "1") (pinfunction "1_1") (pintype "passive"))
      (node (ref "R131") (pin "2") (pinfunction "2_2") (pintype "passive"))
      (node (ref "R132") (pin "1") (pinfunction "1_1") (pintype "passive"))
      (node (ref "R133") (pin "2") (pinfunction "2_2") (pintype "passive"))
      (node (ref "U9") (pin "24") (pinfunction "LED_LINK1000_24") (pintype "passive"))
    )
    (net (code "38") (name "/LED_ACT") (class "Default")
      (node (ref "C270") (pin "2") (pinfunction "2_2") (pintype "passive"))
      (node (ref "R127") (pin "1") (pinfunction "1_1") (pintype "passive"))
      (node (ref "R130") (pin "1") (pinfunction "1_1") (pintype "passive"))
      (node (ref "R134") (pin "2") (pinfunction "2_2") (pintype "passive"))
      (node (ref "U9") (pin "23") (pinfunction "LED_ACT_23") (pintype "passive"))
    )
    (net (code "39") (name "/LINKACT") (class "Default")
      (node (ref "J12") (pin "16") (pinfunction "16_16") (pintype "passive"))
      (node (ref "R130") (pin "2") (pinfunction "2_2") (pintype "passive"))
    )
    (net (code "40") (name "/SPD_10_100") (class "Default")
      (node (ref "J12") (pin "14") (pinfunction "14_14") (pintype "passive"))
      (node (ref "R128") (pin "2") (pinfunction "2_2") (pintype "passive"))
    )
    (net (code "42") (name "1V8") (class "Default")
      (node (ref "R123") (pin "2") (pinfunction "2_2") (pintype "passive"))
    )
    (net (code "43") (name "3V3") (class "Default")
      (node (ref "C254") (pin "2") (pinfunction "2_2") (pintype "passive"))
      (node (ref "C255") (pin "2") (pinfunction "2_2") (pintype "passive"))
      (node (ref "D7") (pin "1") (pinfunction "K_1") (pintype "passive"))
      (node (ref "L13") (pin "1") (pinfunction "1_1") (pintype "passive"))
      (node (ref "R122") (pin "2") (pinfunction "2_2") (pintype "passive"))
      (node (ref "R125") (pin "2") (pinfunction "2_2") (pintype "passive"))
      (node (ref "U9") (pin "4") (pinfunction "VDD33_4") (pintype "passive"))
    )
    (net (code "44") (name "ATH_AVDD33") (class "Default")
      (node (ref "C256") (pin "2") (pinfunction "2_2") (pintype "passive"))
      (node (ref "C257") (pin "2") (pinfunction "2_2") (pintype "passive"))
      (node (ref "L13") (pin "2") (pinfunction "2_2") (pintype "passive"))
      (node (ref "U9") (pin "16") (pinfunction "AVDD33_16") (pintype "passive"))
    )
    (net (code "45") (name "ATH_AVDDL") (class "Default")
      (node (ref "C263") (pin "2") (pinfunction "2_2") (pintype "passive"))
      (node (ref "C264") (pin "2") (pinfunction "2_2") (pintype "passive"))
      (node (ref "C265") (pin "2") (pinfunction "2_2") (pintype "passive"))
      (node (ref "C266") (pin "2") (pinfunction "2_2") (pintype "passive"))
      (node (ref "L15") (pin "2") (pinfunction "2_2") (pintype "passive"))
      (node (ref "U9") (pin "13") (pinfunction "AVDDL_2_13") (pintype "passive"))
      (node (ref "U9") (pin "19") (pinfunction "AVDDL_3_19") (pintype "passive"))
      (node (ref "U9") (pin "44") (pinfunction "AVDDL_4_44") (pintype "passive"))
      (node (ref "U9") (pin "8") (pinfunction "AVDDL_1_8") (pintype "passive"))
    )
    (net (code "46") (name "ATH_ENET1_VDDIO") (class "Default")
      (node (ref "C258") (pin "2") (pinfunction "2_2") (pintype "passive"))
      (node (ref "C259") (pin "2") (pinfunction "2_2") (pintype "passive"))
      (node (ref "R103") (pin "2") (pinfunction "2_2") (pintype "passive"))
      (node (ref "R104") (pin "2") (pinfunction "2_2") (pintype "passive"))
      (node (ref "R105") (pin "2") (pinfunction "2_2") (pintype "passive"))
      (node (ref "R106") (pin "2") (pinfunction "2_2") (pintype "passive"))
      (node (ref "R107") (pin "2") (pinfunction "2_2") (pintype "passive"))
      (node (ref "R108") (pin "2") (pinfunction "2_2") (pintype "passive"))
      (node (ref "R112") (pin "1") (pinfunction "1_1") (pintype "passive"))
    )
    (net (code "47") (name "ATH_PHY_DVDDL_1V1") (class "Default")
      (node (ref "C261") (pin "2") (pinfunction "2_2") (pintype "passive"))
      (node (ref "C262") (pin "2") (pinfunction "2_2") (pintype "passive"))
      (node (ref "L14") (pin "2") (pinfunction "2_2") (pintype "passive"))
      (node (ref "L15") (pin "1") (pinfunction "1_1") (pintype "passive"))
      (node (ref "R124") (pin "2") (pinfunction "2_2") (pintype "passive"))
      (node (ref "U9") (pin "47") (pinfunction "DVDDL_47") (pintype "passive"))
    )
    (net (code "48") (name "ATH_PHY_VDDH") (class "Default")
      (node (ref "C260") (pin "2") (pinfunction "2_2") (pintype "passive"))
      (node (ref "R112") (pin "2") (pinfunction "2_2") (pintype "passive"))
      (node (ref "R126") (pin "2") (pinfunction "2_2") (pintype "passive"))
      (node (ref "R127") (pin "2") (pinfunction "2_2") (pintype "passive"))
    )
    (net (code "49") (name "CHASIS") (class "Default")
      (node (ref "J12") (pin "S1") (pinfunction "SHIELD_S1") (pintype "passive"))
      (node (ref "J12") (pin "S2") (pinfunction "SHIELD_S2") (pintype "passive"))
    )
    (net (code "50") (name "GND") (class "Default")
      (node (ref "C254") (pin "1") (pinfunction "1_1") (pintype "passive"))
      (node (ref "C255") (pin "1") (pinfunction "1_1") (pintype "passive"))
      (node (ref "C256") (pin "1") (pinfunction "1_1") (pintype "passive"))
      (node (ref "C257") (pin "1") (pinfunction "1_1") (pintype "passive"))
      (node (ref "C258") (pin "1") (pinfunction "1_1") (pintype "passive"))
      (node (ref "C259") (pin "1") (pinfunction "1_1") (pintype "passive"))
      (node (ref "C260") (pin "1") (pinfunction "1_1") (pintype "passive"))
      (node (ref "C261") (pin "1") (pinfunction "1_1") (pintype "passive"))
      (node (ref "C262") (pin "1") (pinfunction "1_1") (pintype "passive"))
      (node (ref "C263") (pin "1") (pinfunction "1_1") (pintype "passive"))
      (node (ref "C264") (pin "1") (pinfunction "1_1") (pintype "passive"))
      (node (ref "C265") (pin "1") (pinfunction "1_1") (pintype "passive"))
      (node (ref "C266") (pin "1") (pinfunction "1_1") (pintype "passive"))
      (node (ref "C267") (pin "1") (pinfunction "1_1") (pintype "passive"))
      (node (ref "C268") (pin "1") (pinfunction "1_1") (pintype "passive"))
      (node (ref "C269") (pin "1") (pinfunction "1_1") (pintype "passive"))
      (node (ref "C270") (pin "1") (pinfunction "1_1") (pintype "passive"))
      (node (ref "C271") (pin "1") (pinfunction "1_1") (pintype "passive"))
      (node (ref "C272") (pin "1") (pinfunction "1_1") (pintype "passive"))
      (node (ref "C273") (pin "1") (pinfunction "1_1") (pintype "passive"))
      (node (ref "C274") (pin "1") (pinfunction "1_1") (pintype "passive"))
      (node (ref "D5") (pin "3") (pinfunction "GND1_3") (pintype "power_in"))
      (node (ref "D5") (pin "8") (pinfunction "GND2_8") (pintype "power_in"))
      (node (ref "D6") (pin "3") (pinfunction "GND1_3") (pintype "power_in"))
      (node (ref "D6") (pin "8") (pinfunction "GND2_8") (pintype "power_in"))
      (node (ref "D9") (pin "1") (pinfunction "C_1") (pintype "passive"))
      (node (ref "J12") (pin "13") (pinfunction "13_13") (pintype "passive"))
      (node (ref "J12") (pin "15") (pinfunction "15_15") (pintype "passive"))
      (node (ref "R109") (pin "1") (pinfunction "1_1") (pintype "passive"))
      (node (ref "R110") (pin "1") (pinfunction "1_1") (pintype "passive"))
      (node (ref "R111") (pin "1") (pinfunction "1_1") (pintype "passive"))
      (node (ref "R113") (pin "1") (pinfunction "1_1") (pintype "passive"))
      (node (ref "R114") (pin "1") (pinfunction "1_1") (pintype "passive"))
      (node (ref "R115") (pin "1") (pinfunction "1_1") (pintype "passive"))
      (node (ref "R131") (pin "1") (pinfunction "1_1") (pintype "passive"))
      (node (ref "R133") (pin "1") (pinfunction "1_1") (pintype "passive"))
      (node (ref "R134") (pin "1") (pinfunction "1_1") (pintype "passive"))
      (node (ref "R135") (pin "1") (pinfunction "1_1") (pintype "passive"))
      (node (ref "U9") (pin "49") (pinfunction "EP_(GND)_49") (pintype "passive"))
      (node (ref "Y3") (pin "2") (pinfunction "GND_1_2") (pintype "passive"))
      (node (ref "Y3") (pin "4") (pinfunction "GND_2_4") (pintype "passive"))
    )
    (net (code "51") (name "Net-(D7-A)") (class "Default")
      (node (ref "C268") (pin "2") (pinfunction "2_2") (pintype "passive"))
      (node (ref "C269") (pin "2") (pinfunction "2_2") (pintype "passive"))
      (node (ref "D7") (pin "2") (pinfunction "A_2") (pintype "passive"))
      (node (ref "D8") (pin "2") (pinfunction "A_2") (pintype "passive"))
      (node (ref "R125") (pin "1") (pinfunction "1_1") (pintype "passive"))
      (node (ref "U9") (pin "2") (pinfunction "RSTN_2") (pintype "passive"))
    )
    (net (code "52") (name "Net-(D9-A)") (class "Default")
      (node (ref "D9") (pin "2") (pinfunction "A_2") (pintype "passive"))
      (node (ref "R132") (pin "2") (pinfunction "2_2") (pintype "passive"))
    )
    (net (code "53") (name "Net-(J12-TRCT1)") (class "Default")
      (node (ref "C267") (pin "2") (pinfunction "2_2") (pintype "passive"))
      (node (ref "J12") (pin "1") (pinfunction "TRCT3_1") (pintype "passive"))
      (node (ref "J12") (pin "12") (pinfunction "TRCT1_12") (pintype "passive"))
      (node (ref "J12") (pin "6") (pinfunction "TRCT2_6") (pintype "passive"))
      (node (ref "J12") (pin "7") (pinfunction "TRCT4_7") (pintype "passive"))
    )
    (net (code "54") (name "Net-(U9-CLK_25M)") (class "Default")
      (node (ref "TP44") (pin "1") (pinfunction "1_1") (pintype "passive"))
      (node (ref "U9") (pin "25") (pinfunction "CLK_25M_25") (pintype "passive"))
    )
    (net (code "55") (name "Net-(U9-INT)") (class "Default")
      (node (ref "R123") (pin "1") (pinfunction "1_1") (pintype "passive"))
      (node (ref "R129") (pin "2") (pinfunction "2_2") (pintype "passive"))
      (node (ref "U9") (pin "5") (pinfunction "INT_5") (pintype "passive"))
    )
    (net (code "56") (name "Net-(U9-PPS)") (class "Default")
      (node (ref "TP43") (pin "1") (pinfunction "1_1") (pintype "passive"))
      (node (ref "U9") (pin "22") (pinfunction "PPS_22") (pintype "passive"))
    )
    (net (code "57") (name "Net-(U9-SD)") (class "Default")
      (node (ref "R124") (pin "1") (pinfunction "1_1") (pintype "passive"))
      (node (ref "U9") (pin "41") (pinfunction "SD_41") (pintype "passive"))
    )
    (net (code "58") (name "Net-(U9-WOL_INT)") (class "Default")
      (node (ref "R122") (pin "1") (pinfunction "1_1") (pintype "passive"))
      (node (ref "TP42") (pin "1") (pinfunction "1_1") (pintype "passive"))
      (node (ref "U9") (pin "40") (pinfunction "WOL_INT_40") (pintype "passive"))
    )
    (net (code "59") (name "unconnected-(U9-SIN-Pad45)") (class "Default")
      (node (ref "U9") (pin "45") (pinfunction "SIN_45") (pintype "passive+no_connect"))
    )
    (net (code "60") (name "unconnected-(U9-SIP-Pad46)") (class "Default")
      (node (ref "U9") (pin "46") (pinfunction "SIP_46") (pintype "passive+no_connect"))
    )
    (net (code "61") (name "unconnected-(U9-SON-Pad42)") (class "Default")
      (node (ref "U9") (pin "42") (pinfunction "SON_42") (pintype "passive+no_connect"))
    )
    (net (code "62") (name "unconnected-(U9-SOP-Pad43)") (class "Default")
      (node (ref "U9") (pin "43") (pinfunction "SOP_43") (pintype "passive+no_connect"))
    )
    (net (code "63") (name "unconnected-(U9-VDDH_REG-Pad10)") (class "Default")
      (node (ref "U9") (pin "10") (pinfunction "VDDH_REG_10") (pintype "passive"))
    )
    (net (code "64") (name "unconnected-(U9-VDDIO_REG-Pad29)") (class "Default")
      (node (ref "U9") (pin "29") (pinfunction "VDDIO_REG_29") (pintype "passive"))
    )
  )
)
